# Power.net
KiCad netlist of a schematic drawn in Altium Designer
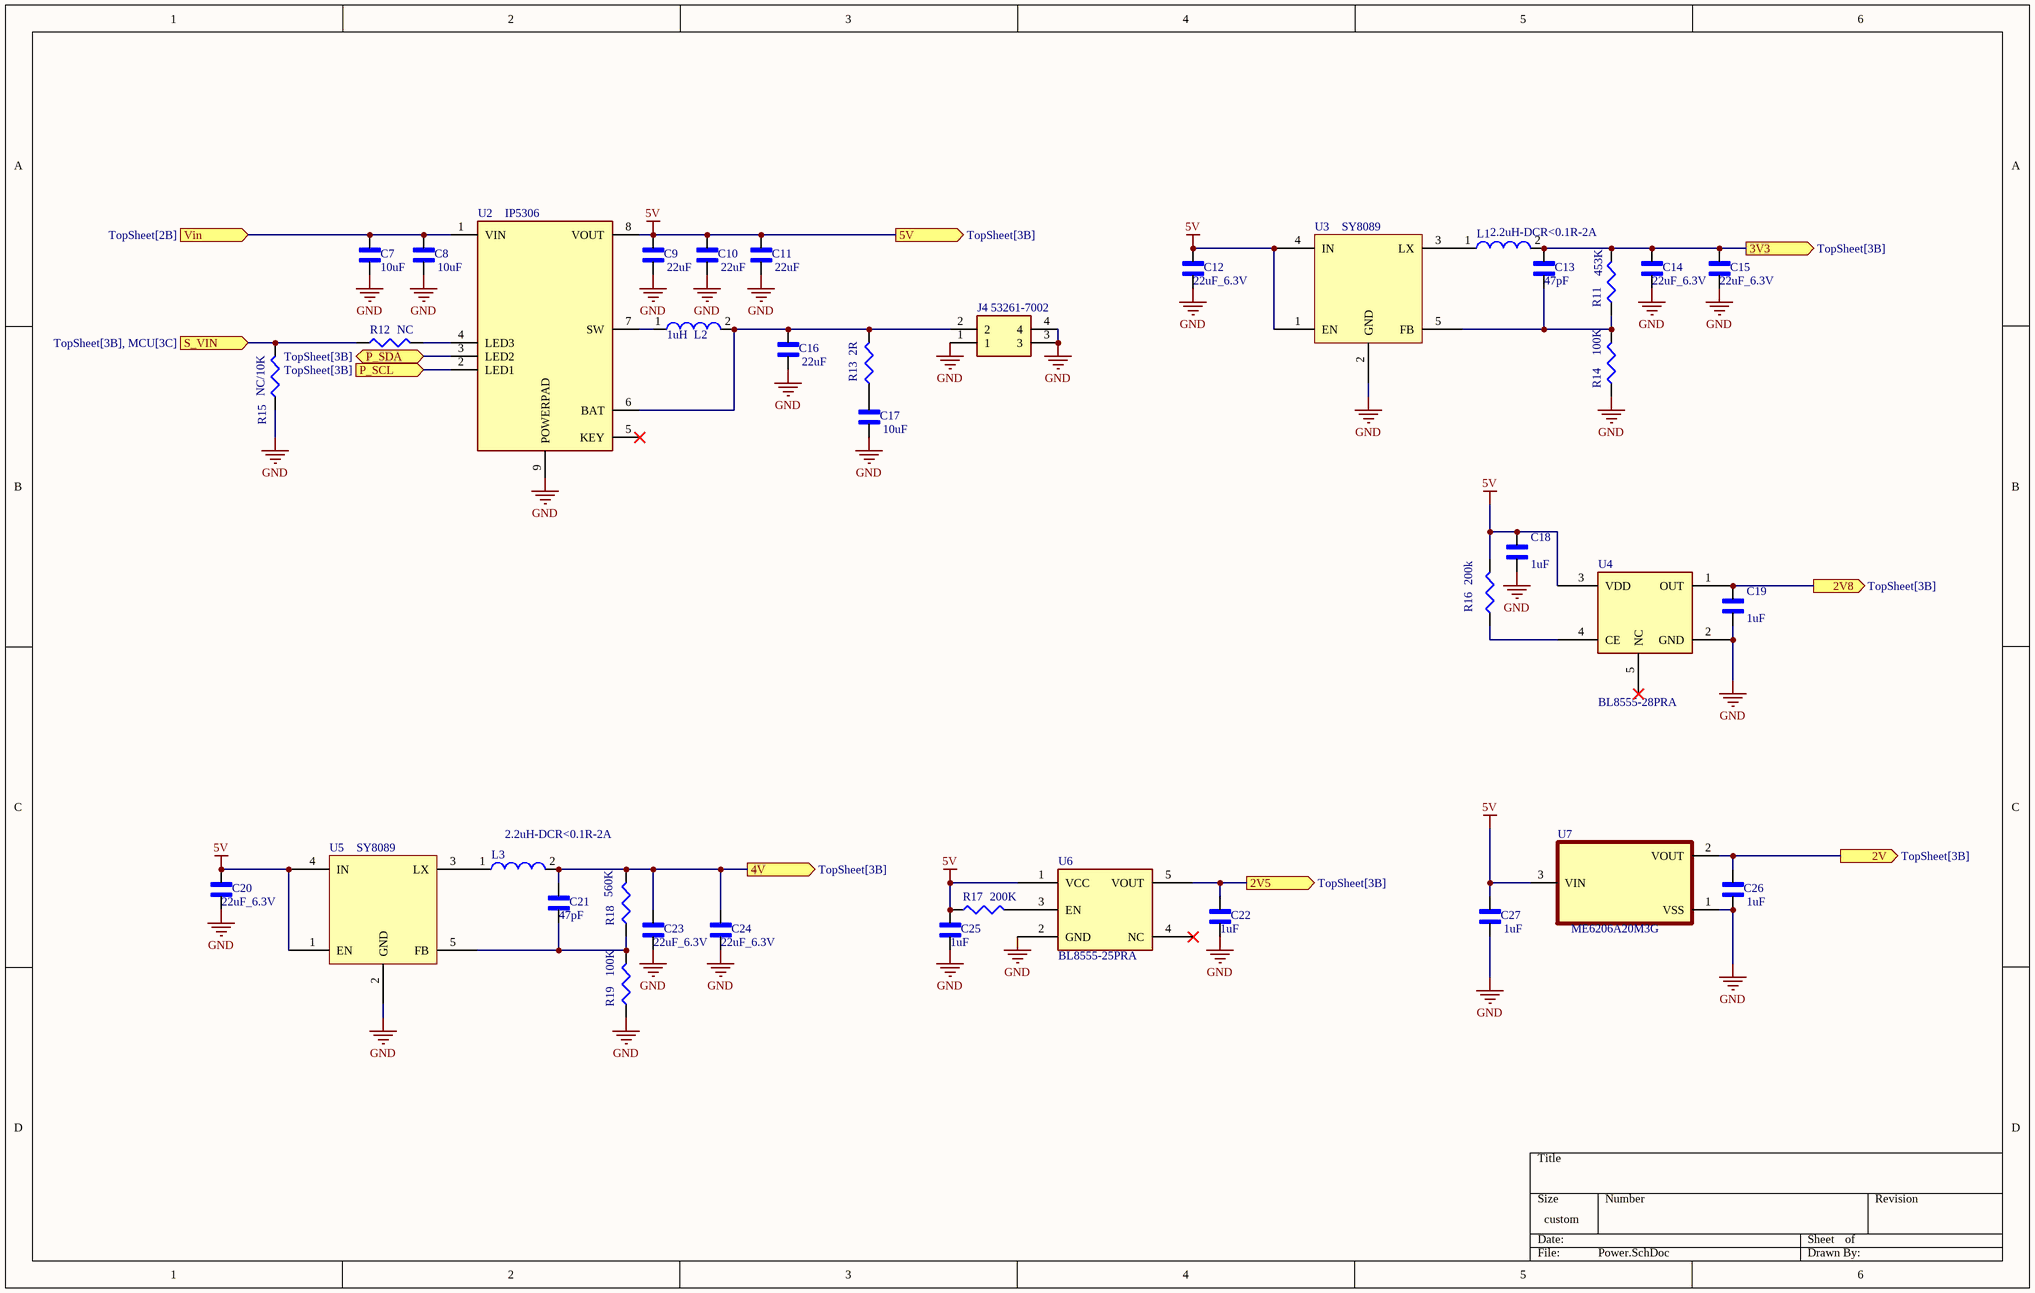
[diagram p0: Power.SchDoc]

(export (version "E")
  (design (tool "Eeschema 10.0.6"))
  (components
    (comp (ref "C7")
      (value "10uF")
      (footprint "C0805")
      (fields (field (name "MF") "Murata") (field (name "MP") "GJM1555C1HR10BB01J"))
      (libsource (lib "common component") (part "Capacitor non polar"))
    )
    (comp (ref "C8")
      (value "10uF")
      (footprint "C0805")
      (fields (field (name "MF") "Murata") (field (name "MP") "GJM1555C1HR10BB01J"))
      (libsource (lib "common component") (part "Capacitor non polar"))
    )
    (comp (ref "C9")
      (value "22uF")
      (footprint "C0805")
      (fields (field (name "MF") "Murata") (field (name "MP") "GJM1555C1HR10BB01J"))
      (libsource (lib "common component") (part "Capacitor non polar"))
    )
    (comp (ref "C10")
      (value "22uF")
      (footprint "C0805")
      (fields (field (name "MF") "Murata") (field (name "MP") "GJM1555C1HR10BB01J"))
      (libsource (lib "common component") (part "Capacitor non polar"))
    )
    (comp (ref "C11")
      (value "22uF")
      (footprint "C0805")
      (fields (field (name "MF") "Murata") (field (name "MP") "GJM1555C1HR10BB01J"))
      (libsource (lib "common component") (part "Capacitor non polar"))
    )
    (comp (ref "C12")
      (value "22uF_6.3V")
      (footprint "C0805")
      (fields (field (name "MF") "Murata") (field (name "MP") "GJM1555C1HR10BB01J"))
      (libsource (lib "common component") (part "Capacitor non polar"))
    )
    (comp (ref "C13")
      (value "47pF")
      (footprint "C0603")
      (fields (field (name "MF") "Murata") (field (name "MP") "GJM1555C1HR10BB01J"))
      (libsource (lib "common component") (part "Capacitor non polar"))
    )
    (comp (ref "C14")
      (value "22uF_6.3V")
      (footprint "C0805")
      (fields (field (name "MF") "Murata") (field (name "MP") "GJM1555C1HR10BB01J"))
      (libsource (lib "common component") (part "Capacitor non polar"))
    )
    (comp (ref "C15")
      (value "22uF_6.3V")
      (footprint "C0805")
      (fields (field (name "MF") "Murata") (field (name "MP") "GJM1555C1HR10BB01J"))
      (libsource (lib "common component") (part "Capacitor non polar"))
    )
    (comp (ref "C16")
      (value "22uF")
      (footprint "C0805")
      (fields (field (name "MF") "Murata") (field (name "MP") "GJM1555C1HR10BB01J"))
      (libsource (lib "common component") (part "Capacitor non polar"))
    )
    (comp (ref "C17")
      (value "10uF")
      (footprint "C0805")
      (fields (field (name "MF") "Murata") (field (name "MP") "GJM1555C1HR10BB01J"))
      (libsource (lib "common component") (part "Capacitor non polar"))
    )
    (comp (ref "C18")
      (value "1uF")
      (footprint "C0603")
      (fields (field (name "MF") "Murata") (field (name "MP") "GJM1555C1HR10BB01J"))
      (libsource (lib "common component") (part "Capacitor non polar"))
    )
    (comp (ref "C19")
      (value "1uF")
      (footprint "C0603")
      (fields (field (name "MF") "Murata") (field (name "MP") "GJM1555C1HR10BB01J"))
      (libsource (lib "common component") (part "Capacitor non polar"))
    )
    (comp (ref "C20")
      (value "22uF_6.3V")
      (footprint "C0805")
      (fields (field (name "MF") "Murata") (field (name "MP") "GJM1555C1HR10BB01J"))
      (libsource (lib "common component") (part "Capacitor non polar"))
    )
    (comp (ref "C21")
      (value "47pF")
      (footprint "C0603")
      (fields (field (name "MF") "Murata") (field (name "MP") "GJM1555C1HR10BB01J"))
      (libsource (lib "common component") (part "Capacitor non polar"))
    )
    (comp (ref "C22")
      (value "1uF")
      (footprint "C0805")
      (fields (field (name "MF") "Murata") (field (name "MP") "GJM1555C1HR10BB01J"))
      (libsource (lib "common component") (part "Capacitor non polar"))
    )
    (comp (ref "C23")
      (value "22uF_6.3V")
      (footprint "C0805")
      (fields (field (name "MF") "Murata") (field (name "MP") "GJM1555C1HR10BB01J"))
      (libsource (lib "common component") (part "Capacitor non polar"))
    )
    (comp (ref "C24")
      (value "22uF_6.3V")
      (footprint "C0805")
      (fields (field (name "MF") "Murata") (field (name "MP") "GJM1555C1HR10BB01J"))
      (libsource (lib "common component") (part "Capacitor non polar"))
    )
    (comp (ref "C25")
      (value "1uF")
      (footprint "C0805")
      (fields (field (name "MF") "Murata") (field (name "MP") "GJM1555C1HR10BB01J"))
      (libsource (lib "common component") (part "Capacitor non polar"))
    )
    (comp (ref "C26")
      (value "1uF")
      (footprint "C0603")
      (fields (field (name "MF") "Murata") (field (name "MP") "GJM1555C1HR10BB01J"))
      (libsource (lib "common component") (part "Capacitor non polar"))
    )
    (comp (ref "C27")
      (value "1uF")
      (footprint "C0603")
      (fields (field (name "MF") "Murata") (field (name "MP") "GJM1555C1HR10BB01J"))
      (libsource (lib "common component") (part "Capacitor non polar"))
    )
    (comp (ref "J4")
      (value "53261-7002")
      (footprint "532617002")
      (description "Headers & Wire Housings PicoBlade SMT RA PKG 0.38 GOLD 2P")
      (fields (field (name "MOUSER PART NUMBER") "538-53261-7002"))
      (libsource (lib "53261-7002") (part "53261-7002"))
    )
    (comp (ref "L1")
      (value "2.2uH-DCR<0.1R-2A")
      (footprint "4.0 mm × 4.0 mm")
      (description "SMD Inductor Generic")
      (fields (field (name "PARTNUMBER") "744043152"))
      (libsource (lib "common component") (part "Inductor"))
    )
    (comp (ref "L2")
      (value "1uH")
      (footprint "4.0 mm × 4.0 mm")
      (description "SMD Inductor Generic")
      (fields (field (name "PARTNUMBER") "744043152"))
      (libsource (lib "common component") (part "Inductor"))
    )
    (comp (ref "L3")
      (value "2.2uH-DCR<0.1R-2A")
      (footprint "4.0 mm × 4.0 mm")
      (description "SMD Inductor Generic")
      (fields (field (name "PARTNUMBER") "744043152"))
      (libsource (lib "common component") (part "Inductor"))
    )
    (comp (ref "R11")
      (value "453K")
      (footprint "R0603")
      (libsource (lib "common component") (part "Resistor"))
    )
    (comp (ref "R12") (value "NC") (footprint "R0603") (libsource (lib "common component") (part "Resistor")))
    (comp (ref "R13") (value "2R") (footprint "R0805") (libsource (lib "common component") (part "Resistor")))
    (comp (ref "R14")
      (value "100K")
      (footprint "R0603")
      (libsource (lib "common component") (part "Resistor"))
    )
    (comp (ref "R15")
      (value "NC/10K")
      (footprint "R0603")
      (libsource (lib "common component") (part "Resistor"))
    )
    (comp (ref "R16")
      (value "200k")
      (footprint "R0603")
      (libsource (lib "common component") (part "Resistor"))
    )
    (comp (ref "R17")
      (value "200K")
      (footprint "R0603")
      (libsource (lib "common component") (part "Resistor"))
    )
    (comp (ref "R18")
      (value "560K")
      (footprint "R0603")
      (libsource (lib "common component") (part "Resistor"))
    )
    (comp (ref "R19")
      (value "100K")
      (footprint "R0603")
      (libsource (lib "common component") (part "Resistor"))
    )
    (comp (ref "U2")
      (value "IP5306")
      (footprint "SOP127P600X165-9N")
      (description "Fully-Integrated Power Bank System-On-Chip with 2.1A charger, 2.4A discharger")
      (fields (field (name "MF") "Injoinic"))
      (libsource (lib "IP5306") (part "IP5306"))
    )
    (comp (ref "U3")
      (value "SY8089")
      (footprint "SOT95P280X145-5N")
      (libsource (lib "SY8089A1") (part "SY8089A1"))
    )
    (comp (ref "U4")
      (value "BL8555-28PRA")
      (footprint "TSOT-23_S5")
      (description "BL8555-28PRA   2.8 V regulator")
      (fields (field (name "MF") "Analog Devices") (field (name "MP") "LT1722CS5#TRMPBF"))
      (libsource (lib "BL8555-28PRA") (part "BL8555-28PRA"))
    )
    (comp (ref "U5")
      (value "SY8089")
      (footprint "SOT95P280X145-5N")
      (libsource (lib "SY8089A1") (part "SY8089A1"))
    )
    (comp (ref "U6")
      (value "BL8555-25PRA")
      (footprint "TSOT-23_S5")
      (description "BL8555-25PRA   2.5 V regulator")
      (fields (field (name "MF") "Analog Devices") (field (name "MP") "LT1722CS5#TRMPBF"))
      (libsource (lib "BL8555-25PRA") (part "BL8555-25PRA"))
    )
    (comp (ref "U7")
      (value "ME6206A20M3G")
      (footprint "SOT95P237X112-3N")
      (description "2V regulator MICRONE(Nanjing Micro One Elec) ME6206A20M3G")
      (fields (field (name "MF") "Analog Devices") (field (name "MP") "MAX6006BEUR+T"))
      (libsource (lib "ME6206A20M3G") (part "ME6206A20M3G"))
    )
  )
  (nets
    (net (code "1") (name "/2V") (class "Default")
      (node (ref "C26") (pin "2") (pinfunction "2_2") (pintype "passive"))
      (node (ref "U7") (pin "2") (pinfunction "VOUT_2") (pintype "passive"))
    )
    (net (code "2") (name "/2V5") (class "Default")
      (node (ref "C22") (pin "2") (pinfunction "2_2") (pintype "passive"))
      (node (ref "U6") (pin "5") (pinfunction "VOUT_5") (pintype "passive"))
    )
    (net (code "3") (name "/2V8") (class "Default")
      (node (ref "C19") (pin "2") (pinfunction "2_2") (pintype "passive"))
      (node (ref "U4") (pin "1") (pinfunction "OUT_1") (pintype "passive"))
    )
    (net (code "4") (name "/3V3") (class "Default")
      (node (ref "C13") (pin "2") (pinfunction "2_2") (pintype "passive"))
      (node (ref "C14") (pin "2") (pinfunction "2_2") (pintype "passive"))
      (node (ref "C15") (pin "2") (pinfunction "2_2") (pintype "passive"))
      (node (ref "L1") (pin "2") (pinfunction "2_2") (pintype "passive"))
      (node (ref "R11") (pin "2") (pinfunction "2_2") (pintype "passive"))
    )
    (net (code "5") (name "/4V") (class "Default")
      (node (ref "C21") (pin "2") (pinfunction "2_2") (pintype "passive"))
      (node (ref "C23") (pin "2") (pinfunction "2_2") (pintype "passive"))
      (node (ref "C24") (pin "2") (pinfunction "2_2") (pintype "passive"))
      (node (ref "L3") (pin "2") (pinfunction "2_2") (pintype "passive"))
      (node (ref "R18") (pin "2") (pinfunction "2_2") (pintype "passive"))
    )
    (net (code "6") (name "/P_SCL") (class "Default")
      (node (ref "U2") (pin "2") (pinfunction "LED1_2") (pintype "passive"))
    )
    (net (code "7") (name "/P_SDA") (class "Default")
      (node (ref "U2") (pin "3") (pinfunction "LED2_3") (pintype "passive"))
    )
    (net (code "8") (name "/S_VIN") (class "Default")
      (node (ref "R12") (pin "1") (pinfunction "1_1") (pintype "passive"))
      (node (ref "R15") (pin "2") (pinfunction "2_2") (pintype "passive"))
    )
    (net (code "9") (name "/Vin") (class "Default")
      (node (ref "C7") (pin "2") (pinfunction "2_2") (pintype "passive"))
      (node (ref "C8") (pin "2") (pinfunction "2_2") (pintype "passive"))
      (node (ref "U2") (pin "1") (pinfunction "VIN_1") (pintype "passive"))
    )
    (net (code "10") (name "5V") (class "Default")
      (node (ref "C10") (pin "2") (pinfunction "2_2") (pintype "passive"))
      (node (ref "C11") (pin "2") (pinfunction "2_2") (pintype "passive"))
      (node (ref "C12") (pin "2") (pinfunction "2_2") (pintype "passive"))
      (node (ref "C18") (pin "2") (pinfunction "2_2") (pintype "passive"))
      (node (ref "C20") (pin "2") (pinfunction "2_2") (pintype "passive"))
      (node (ref "C25") (pin "2") (pinfunction "2_2") (pintype "passive"))
      (node (ref "C27") (pin "2") (pinfunction "2_2") (pintype "passive"))
      (node (ref "C9") (pin "2") (pinfunction "2_2") (pintype "passive"))
      (node (ref "R16") (pin "2") (pinfunction "2_2") (pintype "passive"))
      (node (ref "R17") (pin "1") (pinfunction "1_1") (pintype "passive"))
      (node (ref "U2") (pin "8") (pinfunction "VOUT_8") (pintype "passive"))
      (node (ref "U3") (pin "1") (pinfunction "EN_1") (pintype "passive"))
      (node (ref "U3") (pin "4") (pinfunction "IN_4") (pintype "passive"))
      (node (ref "U4") (pin "3") (pinfunction "VDD_3") (pintype "passive"))
      (node (ref "U5") (pin "1") (pinfunction "EN_1") (pintype "passive"))
      (node (ref "U5") (pin "4") (pinfunction "IN_4") (pintype "passive"))
      (node (ref "U6") (pin "1") (pinfunction "VCC_1") (pintype "passive"))
      (node (ref "U7") (pin "3") (pinfunction "VIN_3") (pintype "passive"))
    )
    (net (code "11") (name "GND") (class "Default")
      (node (ref "C10") (pin "1") (pinfunction "1_1") (pintype "passive"))
      (node (ref "C11") (pin "1") (pinfunction "1_1") (pintype "passive"))
      (node (ref "C12") (pin "1") (pinfunction "1_1") (pintype "passive"))
      (node (ref "C14") (pin "1") (pinfunction "1_1") (pintype "passive"))
      (node (ref "C15") (pin "1") (pinfunction "1_1") (pintype "passive"))
      (node (ref "C16") (pin "1") (pinfunction "1_1") (pintype "passive"))
      (node (ref "C17") (pin "1") (pinfunction "1_1") (pintype "passive"))
      (node (ref "C18") (pin "1") (pinfunction "1_1") (pintype "passive"))
      (node (ref "C19") (pin "1") (pinfunction "1_1") (pintype "passive"))
      (node (ref "C20") (pin "1") (pinfunction "1_1") (pintype "passive"))
      (node (ref "C22") (pin "1") (pinfunction "1_1") (pintype "passive"))
      (node (ref "C23") (pin "1") (pinfunction "1_1") (pintype "passive"))
      (node (ref "C24") (pin "1") (pinfunction "1_1") (pintype "passive"))
      (node (ref "C25") (pin "1") (pinfunction "1_1") (pintype "passive"))
      (node (ref "C26") (pin "1") (pinfunction "1_1") (pintype "passive"))
      (node (ref "C27") (pin "1") (pinfunction "1_1") (pintype "passive"))
      (node (ref "C7") (pin "1") (pinfunction "1_1") (pintype "passive"))
      (node (ref "C8") (pin "1") (pinfunction "1_1") (pintype "passive"))
      (node (ref "C9") (pin "1") (pinfunction "1_1") (pintype "passive"))
      (node (ref "J4") (pin "1") (pinfunction "1_1") (pintype "passive"))
      (node (ref "J4") (pin "3") (pinfunction "3_3") (pintype "passive"))
      (node (ref "J4") (pin "4") (pinfunction "4_4") (pintype "passive"))
      (node (ref "R14") (pin "1") (pinfunction "1_1") (pintype "passive"))
      (node (ref "R15") (pin "1") (pinfunction "1_1") (pintype "passive"))
      (node (ref "R19") (pin "1") (pinfunction "1_1") (pintype "passive"))
      (node (ref "U2") (pin "9") (pinfunction "POWERPAD_9") (pintype "passive"))
      (node (ref "U3") (pin "2") (pinfunction "GND_2") (pintype "passive"))
      (node (ref "U4") (pin "2") (pinfunction "GND_2") (pintype "passive"))
      (node (ref "U5") (pin "2") (pinfunction "GND_2") (pintype "passive"))
      (node (ref "U6") (pin "2") (pinfunction "GND_2") (pintype "passive"))
      (node (ref "U7") (pin "1") (pinfunction "VSS_1") (pintype "passive"))
    )
    (net (code "12") (name "Net-(C17-Pad2)") (class "Default")
      (node (ref "C17") (pin "2") (pinfunction "2_2") (pintype "passive"))
      (node (ref "R13") (pin "1") (pinfunction "1_1") (pintype "passive"))
    )
    (net (code "13") (name "Net-(U2-BAT)") (class "Default")
      (node (ref "C16") (pin "2") (pinfunction "2_2") (pintype "passive"))
      (node (ref "J4") (pin "2") (pinfunction "2_2") (pintype "passive"))
      (node (ref "L2") (pin "2") (pinfunction "2_2") (pintype "passive"))
      (node (ref "R13") (pin "2") (pinfunction "2_2") (pintype "passive"))
      (node (ref "U2") (pin "6") (pinfunction "BAT_6") (pintype "passive"))
    )
    (net (code "14") (name "Net-(U2-LED3)") (class "Default")
      (node (ref "R12") (pin "2") (pinfunction "2_2") (pintype "passive"))
      (node (ref "U2") (pin "4") (pinfunction "LED3_4") (pintype "passive"))
    )
    (net (code "15") (name "Net-(U2-SW)") (class "Default")
      (node (ref "L2") (pin "1") (pinfunction "1_1") (pintype "passive"))
      (node (ref "U2") (pin "7") (pinfunction "SW_7") (pintype "passive"))
    )
    (net (code "16") (name "Net-(U3-FB)") (class "Default")
      (node (ref "C13") (pin "1") (pinfunction "1_1") (pintype "passive"))
      (node (ref "R11") (pin "1") (pinfunction "1_1") (pintype "passive"))
      (node (ref "R14") (pin "2") (pinfunction "2_2") (pintype "passive"))
      (node (ref "U3") (pin "5") (pinfunction "FB_5") (pintype "passive"))
    )
    (net (code "17") (name "Net-(U3-LX)") (class "Default")
      (node (ref "L1") (pin "1") (pinfunction "1_1") (pintype "passive"))
      (node (ref "U3") (pin "3") (pinfunction "LX_3") (pintype "passive"))
    )
    (net (code "18") (name "Net-(U4-CE)") (class "Default")
      (node (ref "R16") (pin "1") (pinfunction "1_1") (pintype "passive"))
      (node (ref "U4") (pin "4") (pinfunction "CE_4") (pintype "passive"))
    )
    (net (code "19") (name "Net-(U5-FB)") (class "Default")
      (node (ref "C21") (pin "1") (pinfunction "1_1") (pintype "passive"))
      (node (ref "R18") (pin "1") (pinfunction "1_1") (pintype "passive"))
      (node (ref "R19") (pin "2") (pinfunction "2_2") (pintype "passive"))
      (node (ref "U5") (pin "5") (pinfunction "FB_5") (pintype "passive"))
    )
    (net (code "20") (name "Net-(U5-LX)") (class "Default")
      (node (ref "L3") (pin "1") (pinfunction "1_1") (pintype "passive"))
      (node (ref "U5") (pin "3") (pinfunction "LX_3") (pintype "passive"))
    )
    (net (code "21") (name "Net-(U6-EN)") (class "Default")
      (node (ref "R17") (pin "2") (pinfunction "2_2") (pintype "passive"))
      (node (ref "U6") (pin "3") (pinfunction "EN_3") (pintype "passive"))
    )
    (net (code "22") (name "unconnected-(U2-KEY-Pad5)") (class "Default")
      (node (ref "U2") (pin "5") (pinfunction "KEY_5") (pintype "passive+no_connect"))
    )
    (net (code "23") (name "unconnected-(U4-NC-Pad5)") (class "Default")
      (node (ref "U4") (pin "5") (pinfunction "NC_5") (pintype "passive+no_connect"))
    )
    (net (code "24") (name "unconnected-(U6-NC-Pad4)") (class "Default")
      (node (ref "U6") (pin "4") (pinfunction "NC_4") (pintype "passive+no_connect"))
    )
  )
)
